# Power.net
KiCad netlist of a schematic drawn in Altium Designer
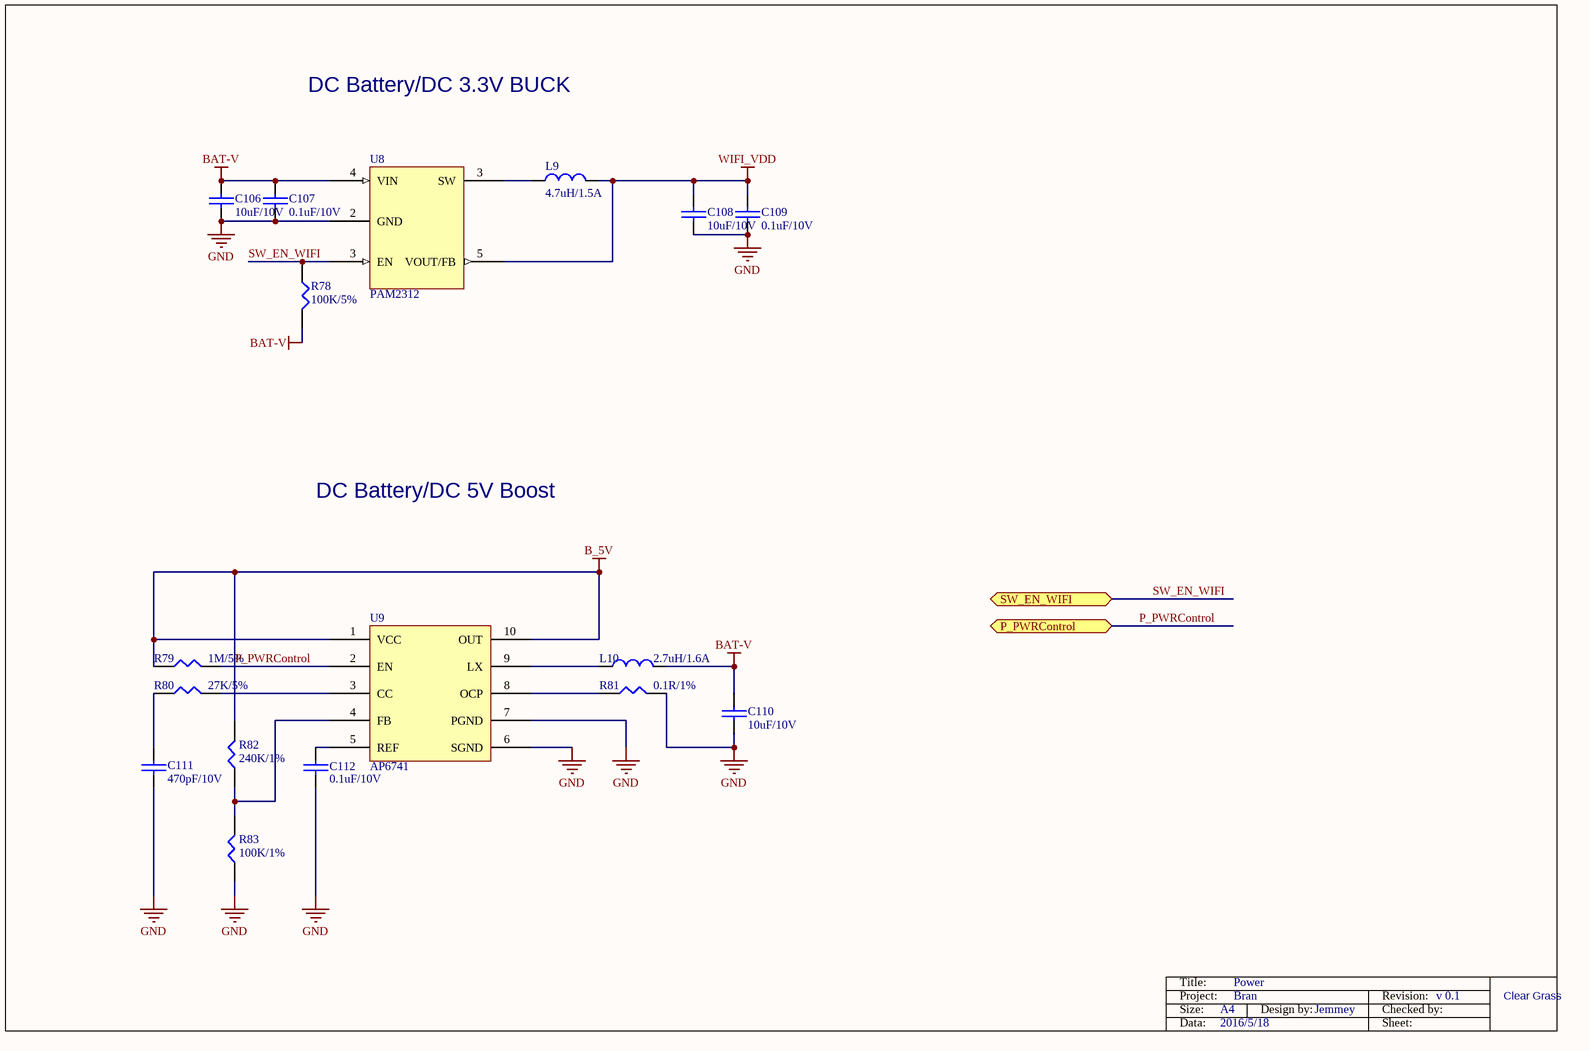
[diagram p0: Power.SchDoc]

(export (version "E")
  (design (tool "Eeschema 10.0.6"))
  (components
    (comp (ref "C106")
      (value "10uF/10V")
      (footprint "0402C")
      (description "厂家：Murata，型号：GRM155R71A104KA01D")
      (libsource (lib "*") (part "CAP"))
    )
    (comp (ref "C107")
      (value "0.1uF/10V")
      (footprint "0402C")
      (description "厂家：Murata，型号：GRM155R71A104KA01D")
      (libsource (lib "*") (part "CAP"))
    )
    (comp (ref "C108")
      (value "10uF/10V")
      (footprint "0402C")
      (description "厂家：Murata，型号：GRM155R71A104KA01D")
      (libsource (lib "*") (part "CAP"))
    )
    (comp (ref "C109")
      (value "0.1uF/10V")
      (footprint "0402C")
      (description "厂家：Murata，型号：GRM155R71A104KA01D")
      (libsource (lib "*") (part "CAP"))
    )
    (comp (ref "C110")
      (value "10uF/10V")
      (footprint "0402C")
      (description "厂家：Murata，型号：GRM155R71A104KA01D")
      (libsource (lib "*") (part "CAP"))
    )
    (comp (ref "C111")
      (value "470pF/10V")
      (footprint "0402C")
      (description "厂家：Murata，型号：GRM155R71A104KA01D")
      (libsource (lib "*") (part "CAP"))
    )
    (comp (ref "C112")
      (value "0.1uF/10V")
      (footprint "0402C")
      (description "厂家：Murata，型号：GRM155R71A104KA01D")
      (libsource (lib "*") (part "CAP"))
    )
    (comp (ref "L9") (value "4.7uH/1.5A") (footprint "Inductance") (libsource (lib "*") (part "CHOKE")))
    (comp (ref "L10") (value "2.7uH/1.6A") (footprint "Inductance") (libsource (lib "*") (part "CHOKE")))
    (comp (ref "R78")
      (value "100K/5%")
      (footprint "0402R")
      (description "厂家：Yageo，型号：RC0402FR-0710KL")
      (libsource (lib "*") (part "RES1"))
    )
    (comp (ref "R79")
      (value "1M/5%")
      (footprint "0402R")
      (description "厂家：Yageo，型号：RC0402FR-0710KL")
      (libsource (lib "*") (part "RES1"))
    )
    (comp (ref "R80")
      (value "27K/5%")
      (footprint "0402R")
      (description "厂家：Yageo，型号：RC0402FR-0710KL")
      (libsource (lib "*") (part "RES1"))
    )
    (comp (ref "R81")
      (value "0.1R/1%")
      (footprint "1206")
      (description "厂家：Yageo，型号：RC0402FR-0710KL")
      (libsource (lib "*") (part "RES1"))
    )
    (comp (ref "R82")
      (value "240K/1%")
      (footprint "0402R")
      (description "厂家：Yageo，型号：RC0402FR-0710KL")
      (libsource (lib "*") (part "RES1"))
    )
    (comp (ref "R83")
      (value "100K/1%")
      (footprint "0402R")
      (description "厂家：Yageo，型号：RC0402FR-0710KL")
      (libsource (lib "*") (part "RES1"))
    )
    (comp (ref "U8")
      (value "PAM2312")
      (footprint "MOLEX_47590001")
      (description "厂家：Diodes，型号：PAM2312TSOT255330")
      (libsource (lib "Bran MB") (part "PAM2312"))
    )
    (comp (ref "U9")
      (value "AP6741")
      (footprint "MOLEX_47590001")
      (description "厂家：Diodes，型号：PAM2401YPADJ")
      (libsource (lib "Bran MB") (part "PAM2401_1"))
    )
  )
  (nets
    (net (code "1") (name "/SW_EN_WIFI") (class "Default")
      (node (ref "R78") (pin "1") (pinfunction "1_1") (pintype "passive"))
      (node (ref "U8") (pin "3") (pinfunction "EN_3") (pintype "input"))
    )
    (net (code "2") (name "BAT-V") (class "Default")
      (node (ref "C106") (pin "2") (pinfunction "2_2") (pintype "passive"))
      (node (ref "C107") (pin "2") (pinfunction "2_2") (pintype "passive"))
      (node (ref "C110") (pin "2") (pinfunction "2_2") (pintype "passive"))
      (node (ref "L10") (pin "2") (pinfunction "2_2") (pintype "passive"))
      (node (ref "R78") (pin "2") (pinfunction "2_2") (pintype "passive"))
      (node (ref "U8") (pin "4") (pinfunction "VIN_4") (pintype "input"))
    )
    (net (code "3") (name "B_5V") (class "Default")
      (node (ref "R79") (pin "1") (pinfunction "1_1") (pintype "passive"))
      (node (ref "R79") (pin "2") (pinfunction "2_2") (pintype "passive"))
      (node (ref "R82") (pin "2") (pinfunction "2_2") (pintype "passive"))
      (node (ref "U9") (pin "1") (pinfunction "VCC_1") (pintype "passive"))
      (node (ref "U9") (pin "10") (pinfunction "OUT_10") (pintype "passive"))
      (node (ref "U9") (pin "2") (pinfunction "EN_2") (pintype "passive"))
    )
    (net (code "4") (name "GND") (class "Default")
      (node (ref "C106") (pin "1") (pinfunction "1_1") (pintype "passive"))
      (node (ref "C107") (pin "1") (pinfunction "1_1") (pintype "passive"))
      (node (ref "C108") (pin "1") (pinfunction "1_1") (pintype "passive"))
      (node (ref "C109") (pin "1") (pinfunction "1_1") (pintype "passive"))
      (node (ref "C110") (pin "1") (pinfunction "1_1") (pintype "passive"))
      (node (ref "C111") (pin "1") (pinfunction "1_1") (pintype "passive"))
      (node (ref "C112") (pin "1") (pinfunction "1_1") (pintype "passive"))
      (node (ref "R81") (pin "2") (pinfunction "2_2") (pintype "passive"))
      (node (ref "R83") (pin "1") (pinfunction "1_1") (pintype "passive"))
      (node (ref "U8") (pin "2") (pinfunction "GND_2") (pintype "passive"))
      (node (ref "U9") (pin "6") (pinfunction "SGND_6") (pintype "passive"))
      (node (ref "U9") (pin "7") (pinfunction "PGND_7") (pintype "passive"))
    )
    (net (code "5") (name "Net-(C111-Pad2)") (class "Default")
      (node (ref "C111") (pin "2") (pinfunction "2_2") (pintype "passive"))
      (node (ref "R80") (pin "1") (pinfunction "1_1") (pintype "passive"))
    )
    (net (code "6") (name "Net-(U8-SW)") (class "Default")
      (node (ref "L9") (pin "1") (pinfunction "1_1") (pintype "passive"))
      (node (ref "U8") (pin "3") (pinfunction "SW_3") (pintype "passive"))
    )
    (net (code "7") (name "Net-(U9-CC)") (class "Default")
      (node (ref "R80") (pin "2") (pinfunction "2_2") (pintype "passive"))
      (node (ref "U9") (pin "3") (pinfunction "CC_3") (pintype "passive"))
    )
    (net (code "8") (name "Net-(U9-FB)") (class "Default")
      (node (ref "R82") (pin "1") (pinfunction "1_1") (pintype "passive"))
      (node (ref "R83") (pin "2") (pinfunction "2_2") (pintype "passive"))
      (node (ref "U9") (pin "4") (pinfunction "FB_4") (pintype "passive"))
    )
    (net (code "9") (name "Net-(U9-LX)") (class "Default")
      (node (ref "L10") (pin "1") (pinfunction "1_1") (pintype "passive"))
      (node (ref "U9") (pin "9") (pinfunction "LX_9") (pintype "passive"))
    )
    (net (code "10") (name "Net-(U9-OCP)") (class "Default")
      (node (ref "R81") (pin "1") (pinfunction "1_1") (pintype "passive"))
      (node (ref "U9") (pin "8") (pinfunction "OCP_8") (pintype "passive"))
    )
    (net (code "11") (name "Net-(U9-REF)") (class "Default")
      (node (ref "C112") (pin "2") (pinfunction "2_2") (pintype "passive"))
      (node (ref "U9") (pin "5") (pinfunction "REF_5") (pintype "passive"))
    )
    (net (code "12") (name "WIFI_VDD") (class "Default")
      (node (ref "C108") (pin "2") (pinfunction "2_2") (pintype "passive"))
      (node (ref "C109") (pin "2") (pinfunction "2_2") (pintype "passive"))
      (node (ref "L9") (pin "2") (pinfunction "2_2") (pintype "passive"))
      (node (ref "U8") (pin "5") (pinfunction "VOUT/FB_5") (pintype "output"))
    )
  )
)
